# XC3S400.net
KiCad netlist of a schematic drawn in Altium Designer
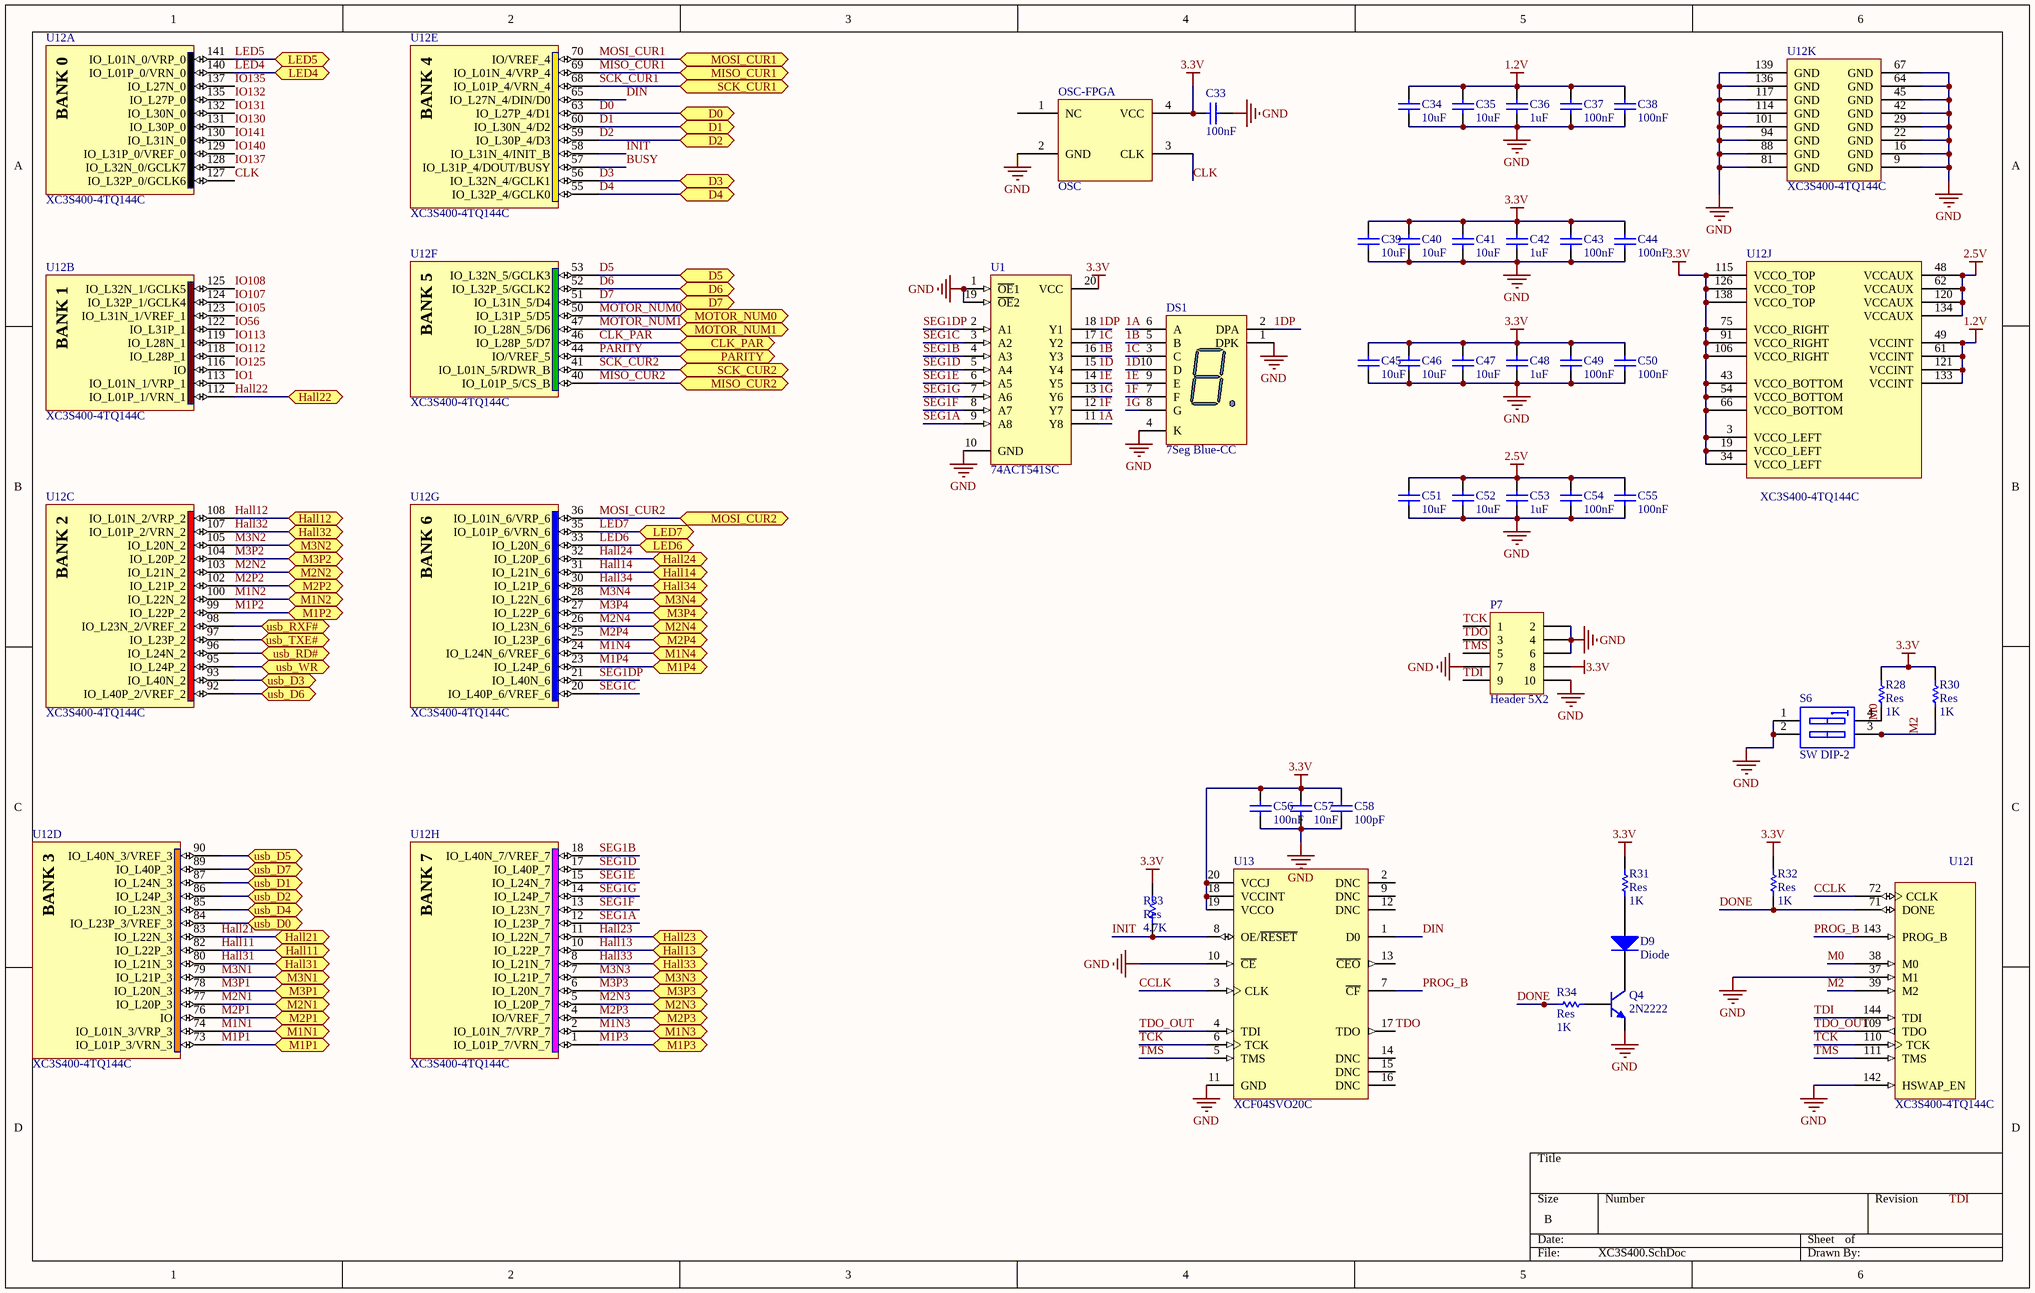
[diagram p0: XC3S400.SchDoc]

(export (version "E")
  (design (tool "Eeschema 10.0.6"))
  (components
    (comp (ref "C33")
      (value "100nF")
      (footprint "2012[0805]")
      (description "Capacitor")
      (fields (field (name "Comment") "Cap_UP") (field (name "PUBLISHER") "Altium Limited"))
      (libsource (lib "KN2CLib") (part "Cap_UP"))
    )
    (comp (ref "C34")
      (value "10uF")
      (footprint "2012[0805]")
      (description "Capacitor")
      (fields (field (name "Comment") "Cap_UP") (field (name "PUBLISHER") "Altium Limited"))
      (libsource (lib "KN2CLib") (part "Cap_UP"))
    )
    (comp (ref "C35")
      (value "10uF")
      (footprint "2012[0805]")
      (description "Capacitor")
      (fields (field (name "Comment") "Cap_UP") (field (name "PUBLISHER") "Altium Limited"))
      (libsource (lib "KN2CLib") (part "Cap_UP"))
    )
    (comp (ref "C36")
      (value "1uF")
      (footprint "2012[0805]")
      (description "Capacitor")
      (fields (field (name "Comment") "Cap_UP") (field (name "PUBLISHER") "Altium Limited"))
      (libsource (lib "KN2CLib") (part "Cap_UP"))
    )
    (comp (ref "C37")
      (value "100nF")
      (footprint "2012[0805]")
      (description "Capacitor")
      (fields (field (name "Comment") "Cap_UP") (field (name "PUBLISHER") "Altium Limited"))
      (libsource (lib "KN2CLib") (part "Cap_UP"))
    )
    (comp (ref "C38")
      (value "100nF")
      (footprint "2012[0805]")
      (description "Capacitor")
      (fields (field (name "Comment") "Cap_UP") (field (name "PUBLISHER") "Altium Limited"))
      (libsource (lib "KN2CLib") (part "Cap_UP"))
    )
    (comp (ref "C39")
      (value "10uF")
      (footprint "2012[0805]")
      (description "Capacitor")
      (fields (field (name "Comment") "Cap_UP") (field (name "PUBLISHER") "Altium Limited"))
      (libsource (lib "KN2CLib") (part "Cap_UP"))
    )
    (comp (ref "C40")
      (value "10uF")
      (footprint "2012[0805]")
      (description "Capacitor")
      (fields (field (name "Comment") "Cap_UP") (field (name "PUBLISHER") "Altium Limited"))
      (libsource (lib "KN2CLib") (part "Cap_UP"))
    )
    (comp (ref "C41")
      (value "10uF")
      (footprint "2012[0805]")
      (description "Capacitor")
      (fields (field (name "Comment") "Cap_UP") (field (name "PUBLISHER") "Altium Limited"))
      (libsource (lib "KN2CLib") (part "Cap_UP"))
    )
    (comp (ref "C42")
      (value "1uF")
      (footprint "2012[0805]")
      (description "Capacitor")
      (fields (field (name "Comment") "Cap_UP") (field (name "PUBLISHER") "Altium Limited"))
      (libsource (lib "KN2CLib") (part "Cap_UP"))
    )
    (comp (ref "C43")
      (value "100nF")
      (footprint "2012[0805]")
      (description "Capacitor")
      (fields (field (name "Comment") "Cap_UP") (field (name "PUBLISHER") "Altium Limited"))
      (libsource (lib "KN2CLib") (part "Cap_UP"))
    )
    (comp (ref "C44")
      (value "100nF")
      (footprint "2012[0805]")
      (description "Capacitor")
      (fields (field (name "Comment") "Cap_UP") (field (name "PUBLISHER") "Altium Limited"))
      (libsource (lib "KN2CLib") (part "Cap_UP"))
    )
    (comp (ref "C45")
      (value "10uF")
      (footprint "2012[0805]")
      (description "Capacitor")
      (fields (field (name "Comment") "Cap_UP") (field (name "PUBLISHER") "Altium Limited"))
      (libsource (lib "KN2CLib") (part "Cap_UP"))
    )
    (comp (ref "C46")
      (value "10uF")
      (footprint "2012[0805]")
      (description "Capacitor")
      (fields (field (name "Comment") "Cap_UP") (field (name "PUBLISHER") "Altium Limited"))
      (libsource (lib "KN2CLib") (part "Cap_UP"))
    )
    (comp (ref "C47")
      (value "10uF")
      (footprint "2012[0805]")
      (description "Capacitor")
      (fields (field (name "Comment") "Cap_UP") (field (name "PUBLISHER") "Altium Limited"))
      (libsource (lib "KN2CLib") (part "Cap_UP"))
    )
    (comp (ref "C48")
      (value "1uF")
      (footprint "2012[0805]")
      (description "Capacitor")
      (fields (field (name "Comment") "Cap_UP") (field (name "PUBLISHER") "Altium Limited"))
      (libsource (lib "KN2CLib") (part "Cap_UP"))
    )
    (comp (ref "C49")
      (value "100nF")
      (footprint "2012[0805]")
      (description "Capacitor")
      (fields (field (name "Comment") "Cap_UP") (field (name "PUBLISHER") "Altium Limited"))
      (libsource (lib "KN2CLib") (part "Cap_UP"))
    )
    (comp (ref "C50")
      (value "100nF")
      (footprint "2012[0805]")
      (description "Capacitor")
      (fields (field (name "Comment") "Cap_UP") (field (name "PUBLISHER") "Altium Limited"))
      (libsource (lib "KN2CLib") (part "Cap_UP"))
    )
    (comp (ref "C51")
      (value "10uF")
      (footprint "2012[0805]")
      (description "Capacitor")
      (fields (field (name "Comment") "Cap_UP") (field (name "PUBLISHER") "Altium Limited"))
      (libsource (lib "KN2CLib") (part "Cap_UP"))
    )
    (comp (ref "C52")
      (value "10uF")
      (footprint "2012[0805]")
      (description "Capacitor")
      (fields (field (name "Comment") "Cap_UP") (field (name "PUBLISHER") "Altium Limited"))
      (libsource (lib "KN2CLib") (part "Cap_UP"))
    )
    (comp (ref "C53")
      (value "1uF")
      (footprint "2012[0805]")
      (description "Capacitor")
      (fields (field (name "Comment") "Cap_UP") (field (name "PUBLISHER") "Altium Limited"))
      (libsource (lib "KN2CLib") (part "Cap_UP"))
    )
    (comp (ref "C54")
      (value "100nF")
      (footprint "2012[0805]")
      (description "Capacitor")
      (fields (field (name "Comment") "Cap_UP") (field (name "PUBLISHER") "Altium Limited"))
      (libsource (lib "KN2CLib") (part "Cap_UP"))
    )
    (comp (ref "C55")
      (value "100nF")
      (footprint "2012[0805]")
      (description "Capacitor")
      (fields (field (name "Comment") "Cap_UP") (field (name "PUBLISHER") "Altium Limited"))
      (libsource (lib "KN2CLib") (part "Cap_UP"))
    )
    (comp (ref "C56")
      (value "100nF")
      (footprint "2012[0805]")
      (description "Capacitor")
      (fields (field (name "Comment") "Cap_UP") (field (name "PUBLISHER") "Altium Limited"))
      (libsource (lib "KN2CLib") (part "Cap_UP"))
    )
    (comp (ref "C57")
      (value "10nF")
      (footprint "2012[0805]")
      (description "Capacitor")
      (fields (field (name "Comment") "Cap_UP") (field (name "PUBLISHER") "Altium Limited"))
      (libsource (lib "KN2CLib") (part "Cap_UP"))
    )
    (comp (ref "C58")
      (value "100pF")
      (footprint "2012[0805]")
      (description "Capacitor")
      (fields (field (name "Comment") "Cap_UP") (field (name "PUBLISHER") "Altium Limited"))
      (libsource (lib "KN2CLib") (part "Cap_UP"))
    )
    (comp (ref "D9")
      (value "Diode")
      (footprint "2012[0805]")
      (description "1 Amp General Purpose Rectifier")
      (fields (field (name "PUBLISHER") "Altium Limited"))
      (libsource (lib "KN2CLib") (part "Diode"))
    )
    (comp (ref "DS1")
      (value "7Seg Blue-CC")
      (footprint "7Segment Small")
      (description "14.2 mm General Purpose Blue 7-Segment Display: CC, RH DP, Gray Surface")
      (fields (field (name "PUBLISHER") "Altium Limited"))
      (libsource (lib "KN2CLib") (part "7Seg Blue-CC_1"))
    )
    (comp (ref "OSC-FPGA") (value "OSC") (footprint "OSC_square") (libsource (lib "KN2CLib") (part "OSC")))
    (comp (ref "P7")
      (value "Header 5X2")
      (footprint "HDR2X5")
      (description "Header, 5-Pin, Dual row")
      (fields (field (name "PUBLISHER") "Altium Limited"))
      (libsource (lib "Miscellaneous Connectors") (part "Header 5X2"))
    )
    (comp (ref "Q4")
      (value "2N2222")
      (footprint "SOT-23")
      (description "NPN Bipolar Transistor")
      (fields (field (name "PUBLISHER") "Altium Limited"))
      (libsource (lib "KN2CLib") (part "2N2222"))
    )
    (comp (ref "R28")
      (value "Res")
      (footprint "2012[0805]")
      (description "Semiconductor Resistor")
      (fields (field (name "ALTIUM_VALUE") "1K") (field (name "PUBLISHER") "Altium Limited"))
      (libsource (lib "KN2CLib") (part "Res"))
    )
    (comp (ref "R30")
      (value "Res")
      (footprint "2012[0805]")
      (description "Semiconductor Resistor")
      (fields (field (name "ALTIUM_VALUE") "1K") (field (name "PUBLISHER") "Altium Limited"))
      (libsource (lib "KN2CLib") (part "Res"))
    )
    (comp (ref "R31")
      (value "Res")
      (footprint "2012[0805]")
      (description "Semiconductor Resistor")
      (fields (field (name "ALTIUM_VALUE") "1K") (field (name "PUBLISHER") "Altium Limited"))
      (libsource (lib "KN2CLib") (part "Res"))
    )
    (comp (ref "R32")
      (value "Res")
      (footprint "2012[0805]")
      (description "Semiconductor Resistor")
      (fields (field (name "ALTIUM_VALUE") "1K") (field (name "PUBLISHER") "Altium Limited"))
      (libsource (lib "KN2CLib") (part "Res"))
    )
    (comp (ref "R33")
      (value "Res")
      (footprint "2012[0805]")
      (description "Semiconductor Resistor")
      (fields (field (name "ALTIUM_VALUE") "4.7K") (field (name "PUBLISHER") "Altium Limited"))
      (libsource (lib "KN2CLib") (part "Res"))
    )
    (comp (ref "R34")
      (value "Res")
      (footprint "2012[0805]")
      (description "Semiconductor Resistor")
      (fields (field (name "ALTIUM_VALUE") "1K") (field (name "PUBLISHER") "Altium Limited"))
      (libsource (lib "KN2CLib") (part "Res"))
    )
    (comp (ref "S6")
      (value "SW DIP-2")
      (footprint "DIP-4")
      (description "DIP Switch, 2 Position, SPST")
      (fields (field (name "PUBLISHER") "Altium Limited"))
      (libsource (lib "Miscellaneous Devices") (part "SW DIP-2"))
    )
    (comp (ref "U1")
      (value "74ACT541SC")
      (footprint "M20B_M")
      (description "Octal Buffer/Line Driver with 3-State Output")
      (fields (field (name "PUBLISHER") "Altium Limited"))
      (libsource (lib "FSC Logic Buffer Line Driver") (part "74ACT541SC"))
    )
    (comp (ref "U12")
      (value "XC3S400-4TQ144C")
      (footprint "TQ144_N")
      (description "Spartan-3 1.2V FPGA, 97 User I/Os, 144-Pin TQFP, Standard Performance, Commercial Grade")
      (fields (field (name "PUBLISHER") "Altium Limited"))
      (libsource (lib "Xilinx Spartan-3") (part "XC3S400-4TQ144C"))
    )
    (comp (ref "U13")
      (value "XCF04SVO20C")
      (footprint "VO20_N")
      (fields (field (name "PUBLISHER") "Altium Limited"))
      (libsource (lib "Xilinx XCF") (part "XCF04SVO20C"))
    )
  )
  (nets
    (net (code "1") (name "/1A") (class "Default")
      (node (ref "DS1") (pin "6") (pinfunction "A_6") (pintype "passive"))
      (node (ref "U1") (pin "11") (pinfunction "Y8_11") (pintype "tri_state"))
    )
    (net (code "2") (name "/1B") (class "Default")
      (node (ref "DS1") (pin "5") (pinfunction "B_5") (pintype "passive"))
      (node (ref "U1") (pin "16") (pinfunction "Y3_16") (pintype "tri_state"))
    )
    (net (code "3") (name "/1C") (class "Default")
      (node (ref "DS1") (pin "3") (pinfunction "C_3") (pintype "passive"))
      (node (ref "U1") (pin "17") (pinfunction "Y2_17") (pintype "tri_state"))
    )
    (net (code "4") (name "/1D") (class "Default")
      (node (ref "DS1") (pin "10") (pinfunction "D_10") (pintype "passive"))
      (node (ref "U1") (pin "15") (pinfunction "Y4_15") (pintype "tri_state"))
    )
    (net (code "5") (name "/1DP") (class "Default")
      (node (ref "DS1") (pin "2") (pinfunction "DPA_2") (pintype "passive"))
      (node (ref "U1") (pin "18") (pinfunction "Y1_18") (pintype "tri_state"))
    )
    (net (code "6") (name "/1E") (class "Default")
      (node (ref "DS1") (pin "9") (pinfunction "E_9") (pintype "passive"))
      (node (ref "U1") (pin "14") (pinfunction "Y5_14") (pintype "tri_state"))
    )
    (net (code "7") (name "/1F") (class "Default")
      (node (ref "DS1") (pin "7") (pinfunction "F_7") (pintype "passive"))
      (node (ref "U1") (pin "12") (pinfunction "Y7_12") (pintype "tri_state"))
    )
    (net (code "8") (name "/1G") (class "Default")
      (node (ref "DS1") (pin "8") (pinfunction "G_8") (pintype "passive"))
      (node (ref "U1") (pin "13") (pinfunction "Y6_13") (pintype "tri_state"))
    )
    (net (code "9") (name "/BUSY") (class "Default")
      (node (ref "U12") (pin "57") (pinfunction "IO_L31P_4/DOUT/BUSY_57") (pintype "bidirectional"))
    )
    (net (code "10") (name "/CCLK") (class "Default")
      (node (ref "U12") (pin "72") (pinfunction "CCLK_72") (pintype "bidirectional"))
      (node (ref "U13") (pin "3") (pinfunction "CLK_3") (pintype "input"))
    )
    (net (code "11") (name "/CLK") (class "Default")
      (node (ref "OSC-FPGA") (pin "3") (pinfunction "CLK_3") (pintype "passive"))
      (node (ref "U12") (pin "127") (pinfunction "IO_L32P_0/GCLK6_127") (pintype "bidirectional"))
    )
    (net (code "12") (name "/CLK_PAR") (class "Default")
      (node (ref "U12") (pin "46") (pinfunction "IO_L28P_5/D7_46") (pintype "bidirectional"))
    )
    (net (code "13") (name "/D0") (class "Default")
      (node (ref "U12") (pin "63") (pinfunction "IO_L27P_4/D1_63") (pintype "bidirectional"))
    )
    (net (code "14") (name "/D1") (class "Default")
      (node (ref "U12") (pin "60") (pinfunction "IO_L30N_4/D2_60") (pintype "bidirectional"))
    )
    (net (code "15") (name "/D2") (class "Default")
      (node (ref "U12") (pin "59") (pinfunction "IO_L30P_4/D3_59") (pintype "bidirectional"))
    )
    (net (code "16") (name "/D3") (class "Default")
      (node (ref "U12") (pin "56") (pinfunction "IO_L32N_4/GCLK1_56") (pintype "bidirectional"))
    )
    (net (code "17") (name "/D4") (class "Default")
      (node (ref "U12") (pin "55") (pinfunction "IO_L32P_4/GCLK0_55") (pintype "bidirectional"))
    )
    (net (code "18") (name "/D5") (class "Default")
      (node (ref "U12") (pin "53") (pinfunction "IO_L32N_5/GCLK3_53") (pintype "bidirectional"))
    )
    (net (code "19") (name "/D6") (class "Default")
      (node (ref "U12") (pin "52") (pinfunction "IO_L32P_5/GCLK2_52") (pintype "bidirectional"))
    )
    (net (code "20") (name "/D7") (class "Default")
      (node (ref "U12") (pin "51") (pinfunction "IO_L31N_5/D4_51") (pintype "bidirectional"))
    )
    (net (code "21") (name "/DIN") (class "Default")
      (node (ref "U12") (pin "65") (pinfunction "IO_L27N_4/DIN/D0_65") (pintype "bidirectional"))
      (node (ref "U13") (pin "1") (pinfunction "D0_1") (pintype "tri_state"))
    )
    (net (code "22") (name "/DONE") (class "Default")
      (node (ref "R32") (pin "1") (pinfunction "1_1") (pintype "passive"))
      (node (ref "R34") (pin "1") (pinfunction "1_1") (pintype "passive"))
      (node (ref "U12") (pin "71") (pinfunction "DONE_71") (pintype "bidirectional"))
    )
    (net (code "23") (name "/Hall11") (class "Default")
      (node (ref "U12") (pin "82") (pinfunction "IO_L22P_3_82") (pintype "bidirectional"))
    )
    (net (code "24") (name "/Hall12") (class "Default")
      (node (ref "U12") (pin "108") (pinfunction "IO_L01N_2/VRP_2_108") (pintype "bidirectional"))
    )
    (net (code "25") (name "/Hall13") (class "Default")
      (node (ref "U12") (pin "10") (pinfunction "IO_L22P_7_10") (pintype "bidirectional"))
    )
    (net (code "26") (name "/Hall14") (class "Default")
      (node (ref "U12") (pin "31") (pinfunction "IO_L21N_6_31") (pintype "bidirectional"))
    )
    (net (code "27") (name "/Hall21") (class "Default")
      (node (ref "U12") (pin "83") (pinfunction "IO_L22N_3_83") (pintype "bidirectional"))
    )
    (net (code "28") (name "/Hall22") (class "Default")
      (node (ref "U12") (pin "112") (pinfunction "IO_L01P_1/VRN_1_112") (pintype "bidirectional"))
    )
    (net (code "29") (name "/Hall23") (class "Default")
      (node (ref "U12") (pin "11") (pinfunction "IO_L22N_7_11") (pintype "bidirectional"))
    )
    (net (code "30") (name "/Hall24") (class "Default")
      (node (ref "U12") (pin "32") (pinfunction "IO_L20P_6_32") (pintype "bidirectional"))
    )
    (net (code "31") (name "/Hall31") (class "Default")
      (node (ref "U12") (pin "80") (pinfunction "IO_L21N_3_80") (pintype "bidirectional"))
    )
    (net (code "32") (name "/Hall32") (class "Default")
      (node (ref "U12") (pin "107") (pinfunction "IO_L01P_2/VRN_2_107") (pintype "bidirectional"))
    )
    (net (code "33") (name "/Hall33") (class "Default")
      (node (ref "U12") (pin "8") (pinfunction "IO_L21N_7_8") (pintype "bidirectional"))
    )
    (net (code "34") (name "/Hall34") (class "Default")
      (node (ref "U12") (pin "30") (pinfunction "IO_L21P_6_30") (pintype "bidirectional"))
    )
    (net (code "35") (name "/INIT") (class "Default")
      (node (ref "R33") (pin "1") (pinfunction "1_1") (pintype "passive"))
      (node (ref "U12") (pin "58") (pinfunction "IO_L31N_4/INIT_B_58") (pintype "bidirectional"))
      (node (ref "U13") (pin "8") (pinfunction "OE/~{RESET}_8") (pintype "bidirectional"))
    )
    (net (code "36") (name "/IO1") (class "Default")
      (node (ref "U12") (pin "113") (pinfunction "IO_L01N_1/VRP_1_113") (pintype "bidirectional"))
    )
    (net (code "37") (name "/IO56") (class "Default")
      (node (ref "U12") (pin "122") (pinfunction "IO_L31P_1_122") (pintype "bidirectional"))
    )
    (net (code "38") (name "/IO105") (class "Default")
      (node (ref "U12") (pin "123") (pinfunction "IO_L31N_1/VREF_1_123") (pintype "bidirectional"))
    )
    (net (code "39") (name "/IO107") (class "Default")
      (node (ref "U12") (pin "124") (pinfunction "IO_L32P_1/GCLK4_124") (pintype "bidirectional"))
    )
    (net (code "40") (name "/IO108") (class "Default")
      (node (ref "U12") (pin "125") (pinfunction "IO_L32N_1/GCLK5_125") (pintype "bidirectional"))
    )
    (net (code "41") (name "/IO112") (class "Default")
      (node (ref "U12") (pin "118") (pinfunction "IO_L28P_1_118") (pintype "bidirectional"))
    )
    (net (code "42") (name "/IO113") (class "Default")
      (node (ref "U12") (pin "119") (pinfunction "IO_L28N_1_119") (pintype "bidirectional"))
    )
    (net (code "43") (name "/IO125") (class "Default")
      (node (ref "U12") (pin "116") (pinfunction "IO_116") (pintype "bidirectional"))
    )
    (net (code "44") (name "/IO130") (class "Default")
      (node (ref "U12") (pin "131") (pinfunction "IO_L30P_0_131") (pintype "bidirectional"))
    )
    (net (code "45") (name "/IO131") (class "Default")
      (node (ref "U12") (pin "132") (pinfunction "IO_L30N_0_132") (pintype "bidirectional"))
    )
    (net (code "46") (name "/IO132") (class "Default")
      (node (ref "U12") (pin "135") (pinfunction "IO_L27P_0_135") (pintype "bidirectional"))
    )
    (net (code "47") (name "/IO135") (class "Default")
      (node (ref "U12") (pin "137") (pinfunction "IO_L27N_0_137") (pintype "bidirectional"))
    )
    (net (code "48") (name "/IO137") (class "Default")
      (node (ref "U12") (pin "128") (pinfunction "IO_L32N_0/GCLK7_128") (pintype "bidirectional"))
    )
    (net (code "49") (name "/IO140") (class "Default")
      (node (ref "U12") (pin "129") (pinfunction "IO_L31P_0/VREF_0_129") (pintype "bidirectional"))
    )
    (net (code "50") (name "/IO141") (class "Default")
      (node (ref "U12") (pin "130") (pinfunction "IO_L31N_0_130") (pintype "bidirectional"))
    )
    (net (code "51") (name "/LED4") (class "Default")
      (node (ref "U12") (pin "140") (pinfunction "IO_L01P_0/VRN_0_140") (pintype "bidirectional"))
    )
    (net (code "52") (name "/LED5") (class "Default")
      (node (ref "U12") (pin "141") (pinfunction "IO_L01N_0/VRP_0_141") (pintype "bidirectional"))
    )
    (net (code "53") (name "/LED6") (class "Default")
      (node (ref "U12") (pin "33") (pinfunction "IO_L20N_6_33") (pintype "bidirectional"))
    )
    (net (code "54") (name "/LED7") (class "Default")
      (node (ref "U12") (pin "35") (pinfunction "IO_L01P_6/VRN_6_35") (pintype "bidirectional"))
    )
    (net (code "55") (name "/M0") (class "Default")
      (node (ref "R28") (pin "1") (pinfunction "1_1") (pintype "passive"))
      (node (ref "S6") (pin "4") (pinfunction "B1_4") (pintype "passive"))
      (node (ref "U12") (pin "38") (pinfunction "M0_38") (pintype "input"))
    )
    (net (code "56") (name "/M1N1") (class "Default")
      (node (ref "U12") (pin "74") (pinfunction "IO_L01N_3/VRP_3_74") (pintype "bidirectional"))
    )
    (net (code "57") (name "/M1N2") (class "Default")
      (node (ref "U12") (pin "100") (pinfunction "IO_L22N_2_100") (pintype "bidirectional"))
    )
    (net (code "58") (name "/M1N3") (class "Default")
      (node (ref "U12") (pin "2") (pinfunction "IO_L01N_7/VRP_7_2") (pintype "bidirectional"))
    )
    (net (code "59") (name "/M1N4") (class "Default")
      (node (ref "U12") (pin "24") (pinfunction "IO_L24N_6/VREF_6_24") (pintype "bidirectional"))
    )
    (net (code "60") (name "/M1P1") (class "Default")
      (node (ref "U12") (pin "73") (pinfunction "IO_L01P_3/VRN_3_73") (pintype "bidirectional"))
    )
    (net (code "61") (name "/M1P2") (class "Default")
      (node (ref "U12") (pin "99") (pinfunction "IO_L22P_2_99") (pintype "bidirectional"))
    )
    (net (code "62") (name "/M1P3") (class "Default")
      (node (ref "U12") (pin "1") (pinfunction "IO_L01P_7/VRN_7_1") (pintype "bidirectional"))
    )
    (net (code "63") (name "/M1P4") (class "Default")
      (node (ref "U12") (pin "23") (pinfunction "IO_L24P_6_23") (pintype "bidirectional"))
    )
    (net (code "64") (name "/M2") (class "Default")
      (node (ref "R30") (pin "1") (pinfunction "1_1") (pintype "passive"))
      (node (ref "S6") (pin "3") (pinfunction "B2_3") (pintype "passive"))
      (node (ref "U12") (pin "39") (pinfunction "M2_39") (pintype "input"))
    )
    (net (code "65") (name "/M2N1") (class "Default")
      (node (ref "U12") (pin "77") (pinfunction "IO_L20P_3_77") (pintype "bidirectional"))
    )
    (net (code "66") (name "/M2N2") (class "Default")
      (node (ref "U12") (pin "103") (pinfunction "IO_L21N_2_103") (pintype "bidirectional"))
    )
    (net (code "67") (name "/M2N3") (class "Default")
      (node (ref "U12") (pin "5") (pinfunction "IO_L20P_7_5") (pintype "bidirectional"))
    )
    (net (code "68") (name "/M2N4") (class "Default")
      (node (ref "U12") (pin "26") (pinfunction "IO_L23N_6_26") (pintype "bidirectional"))
    )
    (net (code "69") (name "/M2P1") (class "Default")
      (node (ref "U12") (pin "76") (pinfunction "IO_76") (pintype "bidirectional"))
    )
    (net (code "70") (name "/M2P2") (class "Default")
      (node (ref "U12") (pin "102") (pinfunction "IO_L21P_2_102") (pintype "bidirectional"))
    )
    (net (code "71") (name "/M2P3") (class "Default")
      (node (ref "U12") (pin "4") (pinfunction "IO/VREF_7_4") (pintype "bidirectional"))
    )
    (net (code "72") (name "/M2P4") (class "Default")
      (node (ref "U12") (pin "25") (pinfunction "IO_L23P_6_25") (pintype "bidirectional"))
    )
    (net (code "73") (name "/M3N1") (class "Default")
      (node (ref "U12") (pin "79") (pinfunction "IO_L21P_3_79") (pintype "bidirectional"))
    )
    (net (code "74") (name "/M3N2") (class "Default")
      (node (ref "U12") (pin "105") (pinfunction "IO_L20N_2_105") (pintype "bidirectional"))
    )
    (net (code "75") (name "/M3N3") (class "Default")
      (node (ref "U12") (pin "7") (pinfunction "IO_L21P_7_7") (pintype "bidirectional"))
    )
    (net (code "76") (name "/M3N4") (class "Default")
      (node (ref "U12") (pin "28") (pinfunction "IO_L22N_6_28") (pintype "bidirectional"))
    )
    (net (code "77") (name "/M3P1") (class "Default")
      (node (ref "U12") (pin "78") (pinfunction "IO_L20N_3_78") (pintype "bidirectional"))
    )
    (net (code "78") (name "/M3P2") (class "Default")
      (node (ref "U12") (pin "104") (pinfunction "IO_L20P_2_104") (pintype "bidirectional"))
    )
    (net (code "79") (name "/M3P3") (class "Default")
      (node (ref "U12") (pin "6") (pinfunction "IO_L20N_7_6") (pintype "bidirectional"))
    )
    (net (code "80") (name "/M3P4") (class "Default")
      (node (ref "U12") (pin "27") (pinfunction "IO_L22P_6_27") (pintype "bidirectional"))
    )
    (net (code "81") (name "/MISO_CUR1") (class "Default")
      (node (ref "U12") (pin "69") (pinfunction "IO_L01N_4/VRP_4_69") (pintype "bidirectional"))
    )
    (net (code "82") (name "/MISO_CUR2") (class "Default")
      (node (ref "U12") (pin "40") (pinfunction "IO_L01P_5/CS_B_40") (pintype "bidirectional"))
    )
    (net (code "83") (name "/MOSI_CUR1") (class "Default")
      (node (ref "U12") (pin "70") (pinfunction "IO/VREF_4_70") (pintype "bidirectional"))
    )
    (net (code "84") (name "/MOSI_CUR2") (class "Default")
      (node (ref "U12") (pin "36") (pinfunction "IO_L01N_6/VRP_6_36") (pintype "bidirectional"))
    )
    (net (code "85") (name "/MOTOR_NUM0") (class "Default")
      (node (ref "U12") (pin "50") (pinfunction "IO_L31P_5/D5_50") (pintype "bidirectional"))
    )
    (net (code "86") (name "/MOTOR_NUM1") (class "Default")
      (node (ref "U12") (pin "47") (pinfunction "IO_L28N_5/D6_47") (pintype "bidirectional"))
    )
    (net (code "87") (name "/PARITY") (class "Default")
      (node (ref "U12") (pin "44") (pinfunction "IO/VREF_5_44") (pintype "bidirectional"))
    )
    (net (code "88") (name "/PROG_B") (class "Default")
      (node (ref "U12") (pin "143") (pinfunction "PROG_B_143") (pintype "input"))
      (node (ref "U13") (pin "7") (pinfunction "~{CF}_7") (pintype "open_collector"))
    )
    (net (code "89") (name "/SCK_CUR1") (class "Default")
      (node (ref "U12") (pin "68") (pinfunction "IO_L01P_4/VRN_4_68") (pintype "bidirectional"))
    )
    (net (code "90") (name "/SCK_CUR2") (class "Default")
      (node (ref "U12") (pin "41") (pinfunction "IO_L01N_5/RDWR_B_41") (pintype "bidirectional"))
    )
    (net (code "91") (name "/SEG1A") (class "Default")
      (node (ref "U1") (pin "9") (pinfunction "A8_9") (pintype "input"))
      (node (ref "U12") (pin "12") (pinfunction "IO_L23P_7_12") (pintype "bidirectional"))
    )
    (net (code "92") (name "/SEG1B") (class "Default")
      (node (ref "U1") (pin "4") (pinfunction "A3_4") (pintype "input"))
      (node (ref "U12") (pin "18") (pinfunction "IO_L40N_7/VREF_7_18") (pintype "bidirectional"))
    )
    (net (code "93") (name "/SEG1C") (class "Default")
      (node (ref "U1") (pin "3") (pinfunction "A2_3") (pintype "input"))
      (node (ref "U12") (pin "20") (pinfunction "IO_L40P_6/VREF_6_20") (pintype "bidirectional"))
    )
    (net (code "94") (name "/SEG1D") (class "Default")
      (node (ref "U1") (pin "5") (pinfunction "A4_5") (pintype "input"))
      (node (ref "U12") (pin "17") (pinfunction "IO_L40P_7_17") (pintype "bidirectional"))
    )
    (net (code "95") (name "/SEG1DP") (class "Default")
      (node (ref "U1") (pin "2") (pinfunction "A1_2") (pintype "input"))
      (node (ref "U12") (pin "21") (pinfunction "IO_L40N_6_21") (pintype "bidirectional"))
    )
    (net (code "96") (name "/SEG1E") (class "Default")
      (node (ref "U1") (pin "6") (pinfunction "A5_6") (pintype "input"))
      (node (ref "U12") (pin "15") (pinfunction "IO_L24N_7_15") (pintype "bidirectional"))
    )
    (net (code "97") (name "/SEG1F") (class "Default")
      (node (ref "U1") (pin "8") (pinfunction "A7_8") (pintype "input"))
      (node (ref "U12") (pin "13") (pinfunction "IO_L23N_7_13") (pintype "bidirectional"))
    )
    (net (code "98") (name "/SEG1G") (class "Default")
      (node (ref "U1") (pin "7") (pinfunction "A6_7") (pintype "input"))
      (node (ref "U12") (pin "14") (pinfunction "IO_L24P_7_14") (pintype "bidirectional"))
    )
    (net (code "99") (name "/TCK") (class "Default")
      (node (ref "P7") (pin "1") (pinfunction "1_1") (pintype "passive"))
      (node (ref "U12") (pin "110") (pinfunction "TCK_110") (pintype "input"))
      (node (ref "U13") (pin "6") (pinfunction "TCK_6") (pintype "input"))
    )
    (net (code "100") (name "/TDI") (class "Default")
      (node (ref "P7") (pin "9") (pinfunction "9_9") (pintype "passive"))
      (node (ref "U12") (pin "144") (pinfunction "TDI_144") (pintype "input"))
    )
    (net (code "101") (name "/TDO") (class "Default")
      (node (ref "P7") (pin "3") (pinfunction "3_3") (pintype "passive"))
      (node (ref "U13") (pin "17") (pinfunction "TDO_17") (pintype "output"))
    )
    (net (code "102") (name "/TDO_OUT") (class "Default")
      (node (ref "U12") (pin "109") (pinfunction "TDO_109") (pintype "output"))
      (node (ref "U13") (pin "4") (pinfunction "TDI_4") (pintype "input"))
    )
    (net (code "103") (name "/TMS") (class "Default")
      (node (ref "P7") (pin "5") (pinfunction "5_5") (pintype "passive"))
      (node (ref "U12") (pin "111") (pinfunction "TMS_111") (pintype "input"))
      (node (ref "U13") (pin "5") (pinfunction "TMS_5") (pintype "input"))
    )
    (net (code "104") (name "/usb_D0") (class "Default")
      (node (ref "U12") (pin "84") (pinfunction "IO_L23P_3/VREF_3_84") (pintype "bidirectional"))
    )
    (net (code "105") (name "/usb_D1") (class "Default")
      (node (ref "U12") (pin "87") (pinfunction "IO_L24N_3_87") (pintype "bidirectional"))
    )
    (net (code "106") (name "/usb_D2") (class "Default")
      (node (ref "U12") (pin "86") (pinfunction "IO_L24P_3_86") (pintype "bidirectional"))
    )
    (net (code "107") (name "/usb_D3") (class "Default")
      (node (ref "U12") (pin "93") (pinfunction "IO_L40N_2_93") (pintype "bidirectional"))
    )
    (net (code "108") (name "/usb_D4") (class "Default")
      (node (ref "U12") (pin "85") (pinfunction "IO_L23N_3_85") (pintype "bidirectional"))
    )
    (net (code "109") (name "/usb_D5") (class "Default")
      (node (ref "U12") (pin "90") (pinfunction "IO_L40N_3/VREF_3_90") (pintype "bidirectional"))
    )
    (net (code "110") (name "/usb_D6") (class "Default")
      (node (ref "U12") (pin "92") (pinfunction "IO_L40P_2/VREF_2_92") (pintype "bidirectional"))
    )
    (net (code "111") (name "/usb_D7") (class "Default")
      (node (ref "U12") (pin "89") (pinfunction "IO_L40P_3_89") (pintype "bidirectional"))
    )
    (net (code "112") (name "/usb_RD#") (class "Default")
      (node (ref "U12") (pin "96") (pinfunction "IO_L24N_2_96") (pintype "bidirectional"))
    )
    (net (code "113") (name "/usb_RXF#") (class "Default")
      (node (ref "U12") (pin "98") (pinfunction "IO_L23N_2/VREF_2_98") (pintype "bidirectional"))
    )
    (net (code "114") (name "/usb_TXE#") (class "Default")
      (node (ref "U12") (pin "97") (pinfunction "IO_L23P_2_97") (pintype "bidirectional"))
    )
    (net (code "115") (name "/usb_WR") (class "Default")
      (node (ref "U12") (pin "95") (pinfunction "IO_L24P_2_95") (pintype "bidirectional"))
    )
    (net (code "116") (name "1.2V") (class "Default")
      (node (ref "C34") (pin "2") (pinfunction "2_2") (pintype "passive"))
      (node (ref "C35") (pin "2") (pinfunction "2_2") (pintype "passive"))
      (node (ref "C36") (pin "2") (pinfunction "2_2") (pintype "passive"))
      (node (ref "C37") (pin "2") (pinfunction "2_2") (pintype "passive"))
      (node (ref "C38") (pin "2") (pinfunction "2_2") (pintype "passive"))
      (node (ref "U12") (pin "121") (pinfunction "VCCINT_121") (pintype "power_in"))
      (node (ref "U12") (pin "133") (pinfunction "VCCINT_133") (pintype "power_in"))
      (node (ref "U12") (pin "49") (pinfunction "VCCINT_49") (pintype "power_in"))
      (node (ref "U12") (pin "61") (pinfunction "VCCINT_61") (pintype "power_in"))
    )
    (net (code "117") (name "2.5V") (class "Default")
      (node (ref "C51") (pin "2") (pinfunction "2_2") (pintype "passive"))
      (node (ref "C52") (pin "2") (pinfunction "2_2") (pintype "passive"))
      (node (ref "C53") (pin "2") (pinfunction "2_2") (pintype "passive"))
      (node (ref "C54") (pin "2") (pinfunction "2_2") (pintype "passive"))
      (node (ref "C55") (pin "2") (pinfunction "2_2") (pintype "passive"))
      (node (ref "U12") (pin "120") (pinfunction "VCCAUX_120") (pintype "power_in"))
      (node (ref "U12") (pin "134") (pinfunction "VCCAUX_134") (pintype "power_in"))
      (node (ref "U12") (pin "48") (pinfunction "VCCAUX_48") (pintype "power_in"))
      (node (ref "U12") (pin "62") (pinfunction "VCCAUX_62") (pintype "power_in"))
    )
    (net (code "118") (name "3.3V") (class "Default")
      (node (ref "C33") (pin "1") (pinfunction "1_1") (pintype "passive"))
      (node (ref "C39") (pin "2") (pinfunction "2_2") (pintype "passive"))
      (node (ref "C40") (pin "2") (pinfunction "2_2") (pintype "passive"))
      (node (ref "C41") (pin "2") (pinfunction "2_2") (pintype "passive"))
      (node (ref "C42") (pin "2") (pinfunction "2_2") (pintype "passive"))
      (node (ref "C43") (pin "2") (pinfunction "2_2") (pintype "passive"))
      (node (ref "C44") (pin "2") (pinfunction "2_2") (pintype "passive"))
      (node (ref "C45") (pin "2") (pinfunction "2_2") (pintype "passive"))
      (node (ref "C46") (pin "2") (pinfunction "2_2") (pintype "passive"))
      (node (ref "C47") (pin "2") (pinfunction "2_2") (pintype "passive"))
      (node (ref "C48") (pin "2") (pinfunction "2_2") (pintype "passive"))
      (node (ref "C49") (pin "2") (pinfunction "2_2") (pintype "passive"))
      (node (ref "C50") (pin "2") (pinfunction "2_2") (pintype "passive"))
      (node (ref "C56") (pin "2") (pinfunction "2_2") (pintype "passive"))
      (node (ref "C57") (pin "2") (pinfunction "2_2") (pintype "passive"))
      (node (ref "C58") (pin "2") (pinfunction "2_2") (pintype "passive"))
      (node (ref "OSC-FPGA") (pin "4") (pinfunction "VCC_4") (pintype "passive"))
      (node (ref "P7") (pin "8") (pinfunction "8_8") (pintype "passive"))
      (node (ref "R28") (pin "2") (pinfunction "2_2") (pintype "passive"))
      (node (ref "R30") (pin "2") (pinfunction "2_2") (pintype "passive"))
      (node (ref "R31") (pin "2") (pinfunction "2_2") (pintype "passive"))
      (node (ref "R32") (pin "2") (pinfunction "2_2") (pintype "passive"))
      (node (ref "R33") (pin "2") (pinfunction "2_2") (pintype "passive"))
      (node (ref "U1") (pin "20") (pinfunction "VCC_20") (pintype "power_in"))
      (node (ref "U12") (pin "106") (pinfunction "VCCO_RIGHT_106") (pintype "power_in"))
      (node (ref "U12") (pin "115") (pinfunction "VCCO_TOP_115") (pintype "power_in"))
      (node (ref "U12") (pin "126") (pinfunction "VCCO_TOP_126") (pintype "power_in"))
      (node (ref "U12") (pin "138") (pinfunction "VCCO_TOP_138") (pintype "power_in"))
      (node (ref "U12") (pin "19") (pinfunction "VCCO_LEFT_19") (pintype "power_in"))
      (node (ref "U12") (pin "3") (pinfunction "VCCO_LEFT_3") (pintype "power_in"))
      (node (ref "U12") (pin "34") (pinfunction "VCCO_LEFT_34") (pintype "power_in"))
      (node (ref "U12") (pin "43") (pinfunction "VCCO_BOTTOM_43") (pintype "power_in"))
      (node (ref "U12") (pin "54") (pinfunction "VCCO_BOTTOM_54") (pintype "power_in"))
      (node (ref "U12") (pin "66") (pinfunction "VCCO_BOTTOM_66") (pintype "power_in"))
      (node (ref "U12") (pin "75") (pinfunction "VCCO_RIGHT_75") (pintype "power_in"))
      (node (ref "U12") (pin "91") (pinfunction "VCCO_RIGHT_91") (pintype "power_in"))
      (node (ref "U13") (pin "18") (pinfunction "VCCINT_18") (pintype "power_in"))
      (node (ref "U13") (pin "19") (pinfunction "VCCO_19") (pintype "power_in"))
      (node (ref "U13") (pin "20") (pinfunction "VCCJ_20") (pintype "power_in"))
    )
    (net (code "119") (name "GND") (class "Default")
      (node (ref "C33") (pin "2") (pinfunction "2_2") (pintype "passive"))
      (node (ref "C34") (pin "1") (pinfunction "1_1") (pintype "passive"))
      (node (ref "C35") (pin "1") (pinfunction "1_1") (pintype "passive"))
      (node (ref "C36") (pin "1") (pinfunction "1_1") (pintype "passive"))
      (node (ref "C37") (pin "1") (pinfunction "1_1") (pintype "passive"))
      (node (ref "C38") (pin "1") (pinfunction "1_1") (pintype "passive"))
      (node (ref "C39") (pin "1") (pinfunction "1_1") (pintype "passive"))
      (node (ref "C40") (pin "1") (pinfunction "1_1") (pintype "passive"))
      (node (ref "C41") (pin "1") (pinfunction "1_1") (pintype "passive"))
      (node (ref "C42") (pin "1") (pinfunction "1_1") (pintype "passive"))
      (node (ref "C43") (pin "1") (pinfunction "1_1") (pintype "passive"))
      (node (ref "C44") (pin "1") (pinfunction "1_1") (pintype "passive"))
      (node (ref "C45") (pin "1") (pinfunction "1_1") (pintype "passive"))
      (node (ref "C46") (pin "1") (pinfunction "1_1") (pintype "passive"))
      (node (ref "C47") (pin "1") (pinfunction "1_1") (pintype "passive"))
      (node (ref "C48") (pin "1") (pinfunction "1_1") (pintype "passive"))
      (node (ref "C49") (pin "1") (pinfunction "1_1") (pintype "passive"))
      (node (ref "C50") (pin "1") (pinfunction "1_1") (pintype "passive"))
      (node (ref "C51") (pin "1") (pinfunction "1_1") (pintype "passive"))
      (node (ref "C52") (pin "1") (pinfunction "1_1") (pintype "passive"))
      (node (ref "C53") (pin "1") (pinfunction "1_1") (pintype "passive"))
      (node (ref "C54") (pin "1") (pinfunction "1_1") (pintype "passive"))
      (node (ref "C55") (pin "1") (pinfunction "1_1") (pintype "passive"))
      (node (ref "C56") (pin "1") (pinfunction "1_1") (pintype "passive"))
      (node (ref "C57") (pin "1") (pinfunction "1_1") (pintype "passive"))
      (node (ref "C58") (pin "1") (pinfunction "1_1") (pintype "passive"))
      (node (ref "DS1") (pin "1") (pinfunction "DPK_1") (pintype "passive"))
      (node (ref "DS1") (pin "4") (pinfunction "K_4") (pintype "passive"))
      (node (ref "OSC-FPGA") (pin "2") (pinfunction "GND_2") (pintype "passive"))
      (node (ref "P7") (pin "10") (pinfunction "10_10") (pintype "passive"))
      (node (ref "P7") (pin "2") (pinfunction "2_2") (pintype "passive"))
      (node (ref "P7") (pin "4") (pinfunction "4_4") (pintype "passive"))
      (node (ref "P7") (pin "6") (pinfunction "6_6") (pintype "passive"))
      (node (ref "P7") (pin "7") (pinfunction "7_7") (pintype "passive"))
      (node (ref "Q4") (pin "3") (pinfunction "E_3") (pintype "passive"))
      (node (ref "S6") (pin "1") (pinfunction "A1_1") (pintype "passive"))
      (node (ref "S6") (pin "2") (pinfunction "A2_2") (pintype "passive"))
      (node (ref "U1") (pin "1") (pinfunction "~{OE}1_1") (pintype "input"))
      (node (ref "U1") (pin "10") (pinfunction "GND_10") (pintype "power_in"))
      (node (ref "U1") (pin "19") (pinfunction "~{OE}2_19") (pintype "input"))
      (node (ref "U12") (pin "101") (pinfunction "GND_101") (pintype "power_in"))
      (node (ref "U12") (pin "114") (pinfunction "GND_114") (pintype "power_in"))
      (node (ref "U12") (pin "117") (pinfunction "GND_117") (pintype "power_in"))
      (node (ref "U12") (pin "136") (pinfunction "GND_136") (pintype "power_in"))
      (node (ref "U12") (pin "139") (pinfunction "GND_139") (pintype "power_in"))
      (node (ref "U12") (pin "142") (pinfunction "HSWAP_EN_142") (pintype "input"))
      (node (ref "U12") (pin "16") (pinfunction "GND_16") (pintype "power_in"))
      (node (ref "U12") (pin "22") (pinfunction "GND_22") (pintype "power_in"))
      (node (ref "U12") (pin "29") (pinfunction "GND_29") (pintype "power_in"))
      (node (ref "U12") (pin "37") (pinfunction "M1_37") (pintype "input"))
      (node (ref "U12") (pin "42") (pinfunction "GND_42") (pintype "power_in"))
      (node (ref "U12") (pin "45") (pinfunction "GND_45") (pintype "power_in"))
      (node (ref "U12") (pin "64") (pinfunction "GND_64") (pintype "power_in"))
      (node (ref "U12") (pin "67") (pinfunction "GND_67") (pintype "power_in"))
      (node (ref "U12") (pin "81") (pinfunction "GND_81") (pintype "power_in"))
      (node (ref "U12") (pin "88") (pinfunction "GND_88") (pintype "power_in"))
      (node (ref "U12") (pin "9") (pinfunction "GND_9") (pintype "power_in"))
      (node (ref "U12") (pin "94") (pinfunction "GND_94") (pintype "power_in"))
      (node (ref "U13") (pin "10") (pinfunction "~{CE}_10") (pintype "input"))
      (node (ref "U13") (pin "11") (pinfunction "GND_11") (pintype "power_in"))
    )
    (net (code "120") (name "Net-(D9-A)") (class "Default")
      (node (ref "D9") (pin "1") (pinfunction "A_1") (pintype "passive"))
      (node (ref "R31") (pin "1") (pinfunction "1_1") (pintype "passive"))
    )
    (net (code "121") (name "Net-(D9-K)") (class "Default")
      (node (ref "D9") (pin "2") (pinfunction "K_2") (pintype "passive"))
      (node (ref "Q4") (pin "1") (pinfunction "C_1") (pintype "passive"))
    )
    (net (code "122") (name "Net-(Q4-B)") (class "Default")
      (node (ref "Q4") (pin "2") (pinfunction "B_2") (pintype "passive"))
      (node (ref "R34") (pin "2") (pinfunction "2_2") (pintype "passive"))
    )
    (net (code "123") (name "unconnected-(OSC-FPGA-NC-Pad1)") (class "Default")
      (node (ref "OSC-FPGA") (pin "1") (pinfunction "NC_1") (pintype "passive"))
    )
    (net (code "124") (name "unconnected-(U13-DNC-Pad2)") (class "Default")
      (node (ref "U13") (pin "2") (pinfunction "DNC_2") (pintype "passive"))
    )
    (net (code "125") (name "unconnected-(U13-DNC-Pad9)") (class "Default")
      (node (ref "U13") (pin "9") (pinfunction "DNC_9") (pintype "passive"))
    )
    (net (code "126") (name "unconnected-(U13-DNC-Pad12)") (class "Default")
      (node (ref "U13") (pin "12") (pinfunction "DNC_12") (pintype "passive"))
    )
    (net (code "127") (name "unconnected-(U13-DNC-Pad14)") (class "Default")
      (node (ref "U13") (pin "14") (pinfunction "DNC_14") (pintype "passive"))
    )
    (net (code "128") (name "unconnected-(U13-DNC-Pad15)") (class "Default")
      (node (ref "U13") (pin "15") (pinfunction "DNC_15") (pintype "passive"))
    )
    (net (code "129") (name "unconnected-(U13-DNC-Pad16)") (class "Default")
      (node (ref "U13") (pin "16") (pinfunction "DNC_16") (pintype "passive"))
    )
    (net (code "130") (name "unconnected-(U13-~{CEO}-Pad13)") (class "Default")
      (node (ref "U13") (pin "13") (pinfunction "~{CEO}_13") (pintype "output"))
    )
  )
)
